# JN5168.net
KiCad netlist of a schematic drawn in Altium Designer
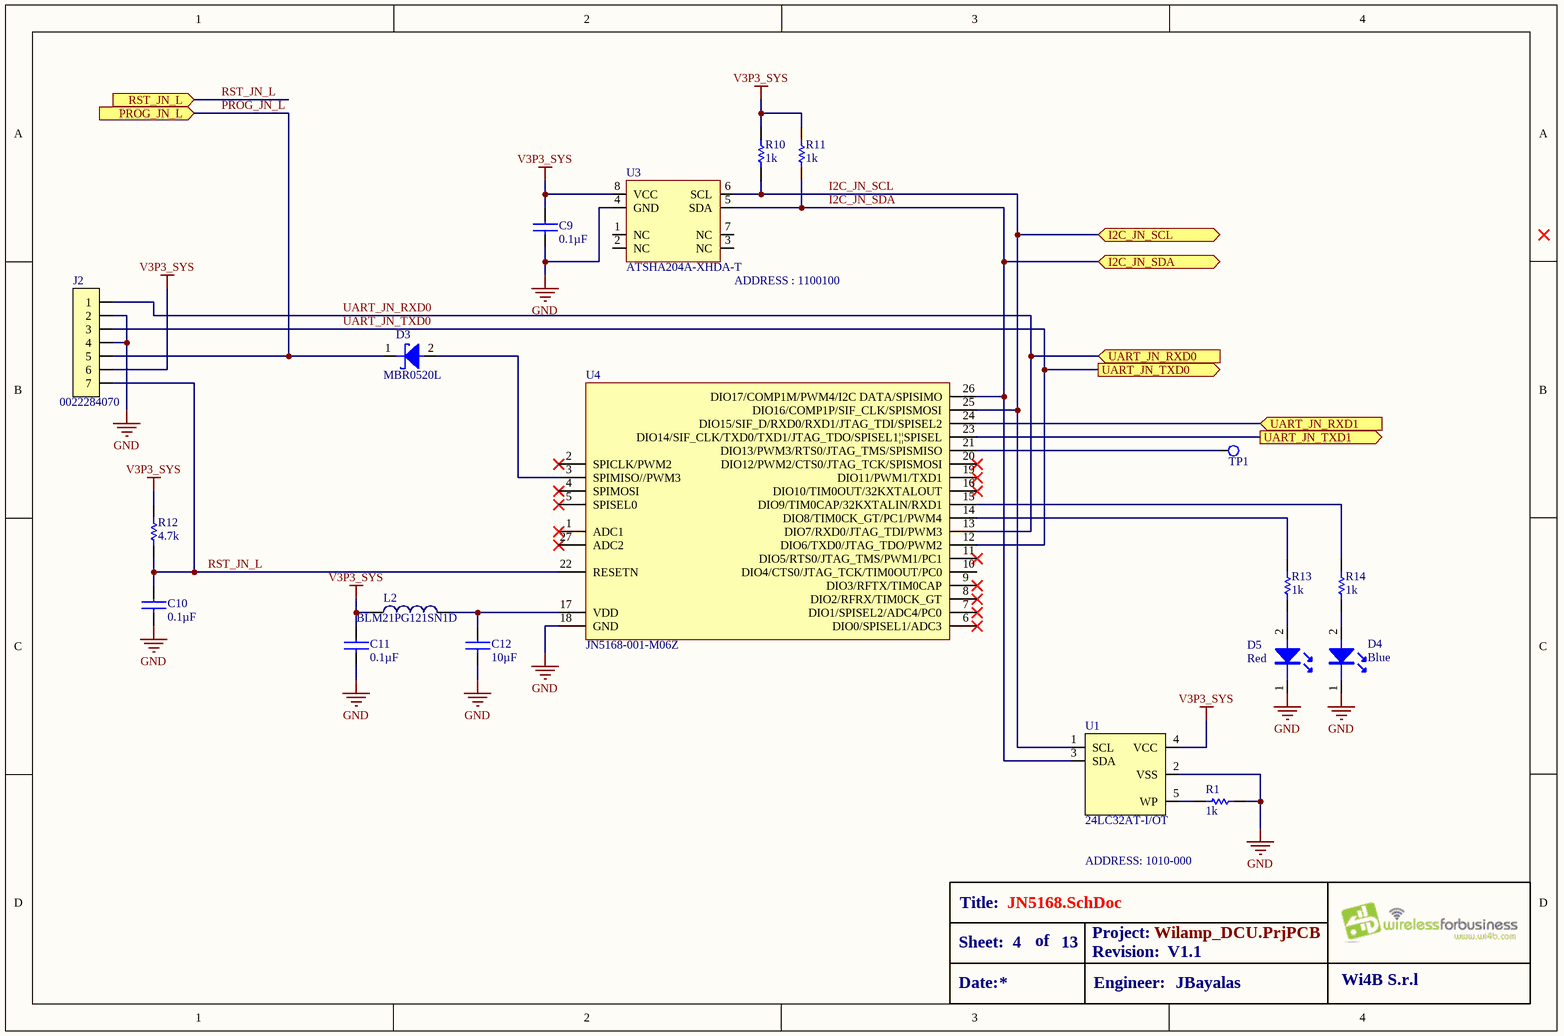
[diagram p0: JN5168.SchDoc]

(export (version "E")
  (design (tool "Eeschema 10.0.6"))
  (components
    (comp (ref "C9")
      (value "0.1µF")
      (footprint "C0402")
      (description "CAP CER 0.1UF 16V X7R 0402")
      (fields (field (name "MPN") "CL05B104KO3LNNC"))
      (libsource (lib "Capacitor") (part "CL05B104KO3LNNC"))
    )
    (comp (ref "C10")
      (value "0.1µF")
      (footprint "C0402")
      (description "CAP CER 0.1UF 16V X7R 0402")
      (fields (field (name "MPN") "CL05B104KO3LNNC"))
      (libsource (lib "Capacitor") (part "CL05B104KO3LNNC"))
    )
    (comp (ref "C11")
      (value "0.1µF")
      (footprint "C0402")
      (description "CAP CER 0.1UF 16V X7R 0402")
      (fields (field (name "MPN") "CL05B104KO3LNNC"))
      (libsource (lib "Capacitor") (part "CL05B104KO3LNNC"))
    )
    (comp (ref "C12")
      (value "10µF")
      (footprint "C0805")
      (description "CAP CER 10UF 6.3V X5R 0805")
      (fields (field (name "MPN") "GRM219R60J106KE19D"))
      (libsource (lib "Capacitor") (part "GRM219R60J106KE19D"))
    )
    (comp (ref "D3")
      (value "MBR0520L")
      (footprint "SOD123")
      (description "DIODE SCHOTTKY 20V 0.5A SOD123")
      (fields (field (name "MPN") "MBR0520L"))
      (libsource (lib "Diode") (part "MBR0520L"))
    )
    (comp (ref "D4")
      (value "Blue")
      (footprint "LED-0603 (BLUE)")
      (description "LED BLUE CLEAR 0603 SMD")
      (fields (field (name "MPN") "LTST-C191TBKT"))
      (libsource (lib "Diode") (part "LTST-C191TBKT"))
    )
    (comp (ref "D5")
      (value "Red")
      (footprint "LED0805 - (RED)")
      (description "LED CHIPLED 633NM RED 0805 SMD")
      (fields (field (name "MPN") "LS R976-NR-1"))
      (libsource (lib "Diode") (part "LS R976-NR-1"))
    )
    (comp (ref "J2")
      (value "*")
      (footprint "0022284070")
      (description "CONN HEADER 7POS .100 VERT TIN")
      (fields (field (name "MPN") "0022284070"))
      (libsource (lib "Connector") (part "0022284070"))
    )
    (comp (ref "L2")
      (value "*")
      (footprint "0805 INDUCTOR")
      (description "FERRITE CHIP 120 OHM 0805")
      (fields (field (name "MPN") "BLM21PG121SN1D"))
      (libsource (lib "Inductor") (part "BLM21PG121SN1D"))
    )
    (comp (ref "R1")
      (value "1k")
      (footprint "R0402")
      (description "RES SMD 1K OHM 1% 1/10W 0402")
      (fields (field (name "MPN") "MCS04020C1001FE000"))
      (libsource (lib "Res") (part "MCS04020C1001FE000"))
    )
    (comp (ref "R10")
      (value "1k")
      (footprint "R0402")
      (description "RES SMD 1K OHM 1% 1/10W 0402")
      (fields (field (name "MPN") "MCS04020C1001FE000"))
      (libsource (lib "Res") (part "MCS04020C1001FE000"))
    )
    (comp (ref "R11")
      (value "1k")
      (footprint "R0402")
      (description "RES SMD 1K OHM 1% 1/10W 0402")
      (fields (field (name "MPN") "MCS04020C1001FE000"))
      (libsource (lib "Res") (part "MCS04020C1001FE000"))
    )
    (comp (ref "R12")
      (value "4.7k")
      (footprint "R0603")
      (description "RES SMD 4.7K OHM 0.1% 1/10W 0603")
      (fields (field (name "MPN") "ERA-3AEB472V"))
      (libsource (lib "Res") (part "ERA-3AEB472V"))
    )
    (comp (ref "R13")
      (value "1k")
      (footprint "R0603")
      (description "RES SMD 1K OHM 1% 1/10W 0603")
      (fields (field (name "MPN") "ERJ-3EKF1001V"))
      (libsource (lib "Res") (part "ERJ-3EKF1001V"))
    )
    (comp (ref "R14")
      (value "1k")
      (footprint "R0603")
      (description "RES SMD 1K OHM 1% 1/10W 0603")
      (fields (field (name "MPN") "ERJ-3EKF1001V"))
      (libsource (lib "Res") (part "ERJ-3EKF1001V"))
    )
    (comp (ref "TP1")
      (value "*")
      (footprint "Test Point 1.27mm")
      (description "Test Point 1.27mm")
      (libsource (lib "Miscellaneous") (part "Test Point"))
    )
    (comp (ref "U1")
      (value "*")
      (footprint "SOT-23-5")
      (description "IC EEPROM 32KBIT 400KHZ SOT23-5")
      (fields (field (name "MPN") "24LC32AT-I/OT"))
      (libsource (lib "IC") (part "24LC32AT-I/OT"))
    )
    (comp (ref "U3")
      (value "ATSHA204A-XHDA-T")
      (footprint "TSSOP-8 (wide Body)")
      (description "IC CRYPTO 4.5KB I2C")
      (fields (field (name "MPN") "ATSHA204A-XHDA-T"))
      (libsource (lib "IC") (part "ATSHA204A-XHDA-T"))
    )
    (comp (ref "U4")
      (value "JN5168-001-M06Z")
      (footprint "JN5168-001-M06Z")
      (description "RF TXRX MODULE 802.15.4 U.FL ANT")
      (fields (field (name "MPN") "JN5168-001-M06Z"))
      (libsource (lib "Module") (part "JN5168-001-M06Z"))
    )
  )
  (nets
    (net (code "1") (name "/I2C_JN_SCL") (class "Default")
      (node (ref "R10") (pin "1") (pinfunction "1_1") (pintype "passive"))
      (node (ref "U1") (pin "1") (pinfunction "SCL_1") (pintype "passive"))
      (node (ref "U3") (pin "6") (pinfunction "SCL_6") (pintype "passive"))
      (node (ref "U4") (pin "25") (pinfunction "DIO16/COMP1P/SIF_CLK/SPISMOSI_25") (pintype "passive"))
    )
    (net (code "2") (name "/I2C_JN_SDA") (class "Default")
      (node (ref "R11") (pin "1") (pinfunction "1_1") (pintype "passive"))
      (node (ref "U1") (pin "3") (pinfunction "SDA_3") (pintype "passive"))
      (node (ref "U3") (pin "5") (pinfunction "SDA_5") (pintype "passive"))
      (node (ref "U4") (pin "26") (pinfunction "DIO17/COMP1M/PWM4/I2C_DATA/SPISIMO_26") (pintype "passive"))
    )
    (net (code "3") (name "/PROG_JN_L") (class "Default")
      (node (ref "D3") (pin "1") (pinfunction "cathode_1") (pintype "passive"))
      (node (ref "J2") (pin "5") (pinfunction "5_5") (pintype "passive"))
    )
    (net (code "4") (name "/RST_JN_L") (class "Default")
      (node (ref "C10") (pin "1") (pinfunction "1_1") (pintype "passive"))
      (node (ref "J2") (pin "7") (pinfunction "7_7") (pintype "passive"))
      (node (ref "R12") (pin "1") (pinfunction "1_1") (pintype "passive"))
      (node (ref "U4") (pin "22") (pinfunction "RESETN_22") (pintype "passive"))
    )
    (net (code "5") (name "/UART_JN_RXD0") (class "Default")
      (node (ref "J2") (pin "1") (pinfunction "1_1") (pintype "passive"))
      (node (ref "U4") (pin "13") (pinfunction "DIO7/RXD0/JTAG_TDI/PWM3_13") (pintype "passive"))
    )
    (net (code "6") (name "/UART_JN_RXD1") (class "Default")
      (node (ref "U4") (pin "24") (pinfunction "DIO15/SIF_D/RXD0/RXD1/JTAG_TDI/SPISEL2_24") (pintype "passive"))
    )
    (net (code "7") (name "/UART_JN_TXD0") (class "Default")
      (node (ref "J2") (pin "3") (pinfunction "3_3") (pintype "passive"))
      (node (ref "U4") (pin "12") (pinfunction "DIO6/TXD0/JTAG_TDO/PWM2_12") (pintype "passive"))
    )
    (net (code "8") (name "/UART_JN_TXD1") (class "Default")
      (node (ref "U4") (pin "23") (pinfunction "DIO14/SIF_CLK/TXD0/TXD1/JTAG_TDO/SPISEL1ΖSPISEL_23") (pintype "passive"))
    )
    (net (code "9") (name "GND") (class "Default")
      (node (ref "C10") (pin "2") (pinfunction "2_2") (pintype "passive"))
      (node (ref "C11") (pin "2") (pinfunction "2_2") (pintype "passive"))
      (node (ref "C12") (pin "2") (pinfunction "2_2") (pintype "passive"))
      (node (ref "C9") (pin "2") (pinfunction "2_2") (pintype "passive"))
      (node (ref "D4") (pin "1") (pinfunction "1_1") (pintype "passive"))
      (node (ref "D5") (pin "1") (pinfunction "1_1") (pintype "passive"))
      (node (ref "J2") (pin "2") (pinfunction "2_2") (pintype "passive"))
      (node (ref "J2") (pin "4") (pinfunction "4_4") (pintype "passive"))
      (node (ref "R1") (pin "2") (pinfunction "2_2") (pintype "passive"))
      (node (ref "U1") (pin "2") (pinfunction "VSS_2") (pintype "passive"))
      (node (ref "U3") (pin "4") (pinfunction "GND_4") (pintype "passive"))
      (node (ref "U4") (pin "18") (pinfunction "GND_18") (pintype "passive"))
    )
    (net (code "10") (name "Net-(D3-anode)") (class "Default")
      (node (ref "D3") (pin "2") (pinfunction "anode_2") (pintype "passive"))
      (node (ref "U4") (pin "3") (pinfunction "SPIMISO//PWM3_3") (pintype "passive"))
    )
    (net (code "11") (name "Net-(D4-Pad2)") (class "Default")
      (node (ref "D4") (pin "2") (pinfunction "2_2") (pintype "passive"))
      (node (ref "R14") (pin "2") (pinfunction "2_2") (pintype "passive"))
    )
    (net (code "12") (name "Net-(D5-Pad2)") (class "Default")
      (node (ref "D5") (pin "2") (pinfunction "2_2") (pintype "passive"))
      (node (ref "R13") (pin "2") (pinfunction "2_2") (pintype "passive"))
    )
    (net (code "13") (name "Net-(U1-WP)") (class "Default")
      (node (ref "R1") (pin "1") (pinfunction "1_1") (pintype "passive"))
      (node (ref "U1") (pin "5") (pinfunction "WP_5") (pintype "passive"))
    )
    (net (code "14") (name "Net-(U4-DIO8{slash}TIM0CK_GT{slash}PC1{slash}PWM4)") (class "Default")
      (node (ref "R13") (pin "1") (pinfunction "1_1") (pintype "passive"))
      (node (ref "U4") (pin "14") (pinfunction "DIO8/TIM0CK_GT/PC1/PWM4_14") (pintype "passive"))
    )
    (net (code "15") (name "Net-(U4-DIO9{slash}TIM0CAP{slash}32KXTALIN{slash}RXD1)") (class "Default")
      (node (ref "R14") (pin "1") (pinfunction "1_1") (pintype "passive"))
      (node (ref "U4") (pin "15") (pinfunction "DIO9/TIM0CAP/32KXTALIN/RXD1_15") (pintype "passive"))
    )
    (net (code "16") (name "Net-(U4-DIO13{slash}PWM3{slash}RTS0{slash}JTAG_TMS{slash}SPISMISO)") (class "Default")
      (node (ref "TP1") (pin "1") (pinfunction "1_1") (pintype "passive"))
      (node (ref "U4") (pin "21") (pinfunction "DIO13/PWM3/RTS0/JTAG_TMS/SPISMISO_21") (pintype "passive"))
    )
    (net (code "17") (name "Net-(U4-VDD)") (class "Default")
      (node (ref "C12") (pin "1") (pinfunction "1_1") (pintype "passive"))
      (node (ref "L2") (pin "1") (pinfunction "1_1") (pintype "passive"))
      (node (ref "U4") (pin "17") (pinfunction "VDD_17") (pintype "passive"))
    )
    (net (code "18") (name "V3P3_SYS") (class "Default")
      (node (ref "C11") (pin "1") (pinfunction "1_1") (pintype "passive"))
      (node (ref "C9") (pin "1") (pinfunction "1_1") (pintype "passive"))
      (node (ref "J2") (pin "6") (pinfunction "6_6") (pintype "passive"))
      (node (ref "L2") (pin "2") (pinfunction "2_2") (pintype "passive"))
      (node (ref "R10") (pin "2") (pinfunction "2_2") (pintype "passive"))
      (node (ref "R11") (pin "2") (pinfunction "2_2") (pintype "passive"))
      (node (ref "R12") (pin "2") (pinfunction "2_2") (pintype "passive"))
      (node (ref "U1") (pin "4") (pinfunction "VCC_4") (pintype "passive"))
      (node (ref "U3") (pin "8") (pinfunction "VCC_8") (pintype "passive"))
    )
    (net (code "19") (name "unconnected-(U3-NC-Pad1)") (class "Default")
      (node (ref "U3") (pin "1") (pinfunction "NC_1") (pintype "passive"))
    )
    (net (code "20") (name "unconnected-(U3-NC-Pad2)") (class "Default")
      (node (ref "U3") (pin "2") (pinfunction "NC_2") (pintype "passive"))
    )
    (net (code "21") (name "unconnected-(U3-NC-Pad3)") (class "Default")
      (node (ref "U3") (pin "3") (pinfunction "NC_3") (pintype "passive"))
    )
    (net (code "22") (name "unconnected-(U3-NC-Pad7)") (class "Default")
      (node (ref "U3") (pin "7") (pinfunction "NC_7") (pintype "passive"))
    )
    (net (code "23") (name "unconnected-(U4-ADC1-Pad1)") (class "Default")
      (node (ref "U4") (pin "1") (pinfunction "ADC1_1") (pintype "passive+no_connect"))
    )
    (net (code "24") (name "unconnected-(U4-ADC2-Pad27)") (class "Default")
      (node (ref "U4") (pin "27") (pinfunction "ADC2_27") (pintype "passive+no_connect"))
    )
    (net (code "25") (name "unconnected-(U4-DIO0{slash}SPISEL1{slash}ADC3-Pad6)") (class "Default")
      (node (ref "U4") (pin "6") (pinfunction "DIO0/SPISEL1/ADC3_6") (pintype "passive+no_connect"))
    )
    (net (code "26") (name "unconnected-(U4-DIO1{slash}SPISEL2{slash}ADC4{slash}PC0-Pad7)") (class "Default")
      (node (ref "U4") (pin "7") (pinfunction "DIO1/SPISEL2/ADC4/PC0_7") (pintype "passive+no_connect"))
    )
    (net (code "27") (name "unconnected-(U4-DIO2{slash}RFRX{slash}TIM0CK_GT-Pad8)") (class "Default")
      (node (ref "U4") (pin "8") (pinfunction "DIO2/RFRX/TIM0CK_GT_8") (pintype "passive+no_connect"))
    )
    (net (code "28") (name "unconnected-(U4-DIO3{slash}RFTX{slash}TIM0CAP-Pad9)") (class "Default")
      (node (ref "U4") (pin "9") (pinfunction "DIO3/RFTX/TIM0CAP_9") (pintype "passive+no_connect"))
    )
    (net (code "29") (name "unconnected-(U4-DIO4{slash}CTS0{slash}JTAG_TCK{slash}TIM0OUT{slash}PC0-Pad10)") (class "Default")
      (node (ref "U4") (pin "10") (pinfunction "DIO4/CTS0/JTAG_TCK/TIM0OUT/PC0_10") (pintype "passive"))
    )
    (net (code "30") (name "unconnected-(U4-DIO5{slash}RTS0{slash}JTAG_TMS{slash}PWM1{slash}PC1-Pad11)") (class "Default")
      (node (ref "U4") (pin "11") (pinfunction "DIO5/RTS0/JTAG_TMS/PWM1/PC1_11") (pintype "passive+no_connect"))
    )
    (net (code "31") (name "unconnected-(U4-DIO10{slash}TIM0OUT{slash}32KXTALOUT-Pad16)") (class "Default")
      (node (ref "U4") (pin "16") (pinfunction "DIO10/TIM0OUT/32KXTALOUT_16") (pintype "passive+no_connect"))
    )
    (net (code "32") (name "unconnected-(U4-DIO11{slash}PWM1{slash}TXD1-Pad19)") (class "Default")
      (node (ref "U4") (pin "19") (pinfunction "DIO11/PWM1/TXD1_19") (pintype "passive+no_connect"))
    )
    (net (code "33") (name "unconnected-(U4-DIO12{slash}PWM2{slash}CTS0{slash}JTAG_TCK{slash}SPISMOSI-Pad20)") (class "Default")
      (node (ref "U4") (pin "20") (pinfunction "DIO12/PWM2/CTS0/JTAG_TCK/SPISMOSI_20") (pintype "passive+no_connect"))
    )
    (net (code "34") (name "unconnected-(U4-SPICLK{slash}PWM2-Pad2)") (class "Default")
      (node (ref "U4") (pin "2") (pinfunction "SPICLK/PWM2_2") (pintype "passive+no_connect"))
    )
    (net (code "35") (name "unconnected-(U4-SPIMOSI-Pad4)") (class "Default")
      (node (ref "U4") (pin "4") (pinfunction "SPIMOSI_4") (pintype "passive+no_connect"))
    )
    (net (code "36") (name "unconnected-(U4-SPISEL0-Pad5)") (class "Default")
      (node (ref "U4") (pin "5") (pinfunction "SPISEL0_5") (pintype "passive+no_connect"))
    )
  )
)
